# version1.net
KiCad netlist of a schematic drawn in EAGLE
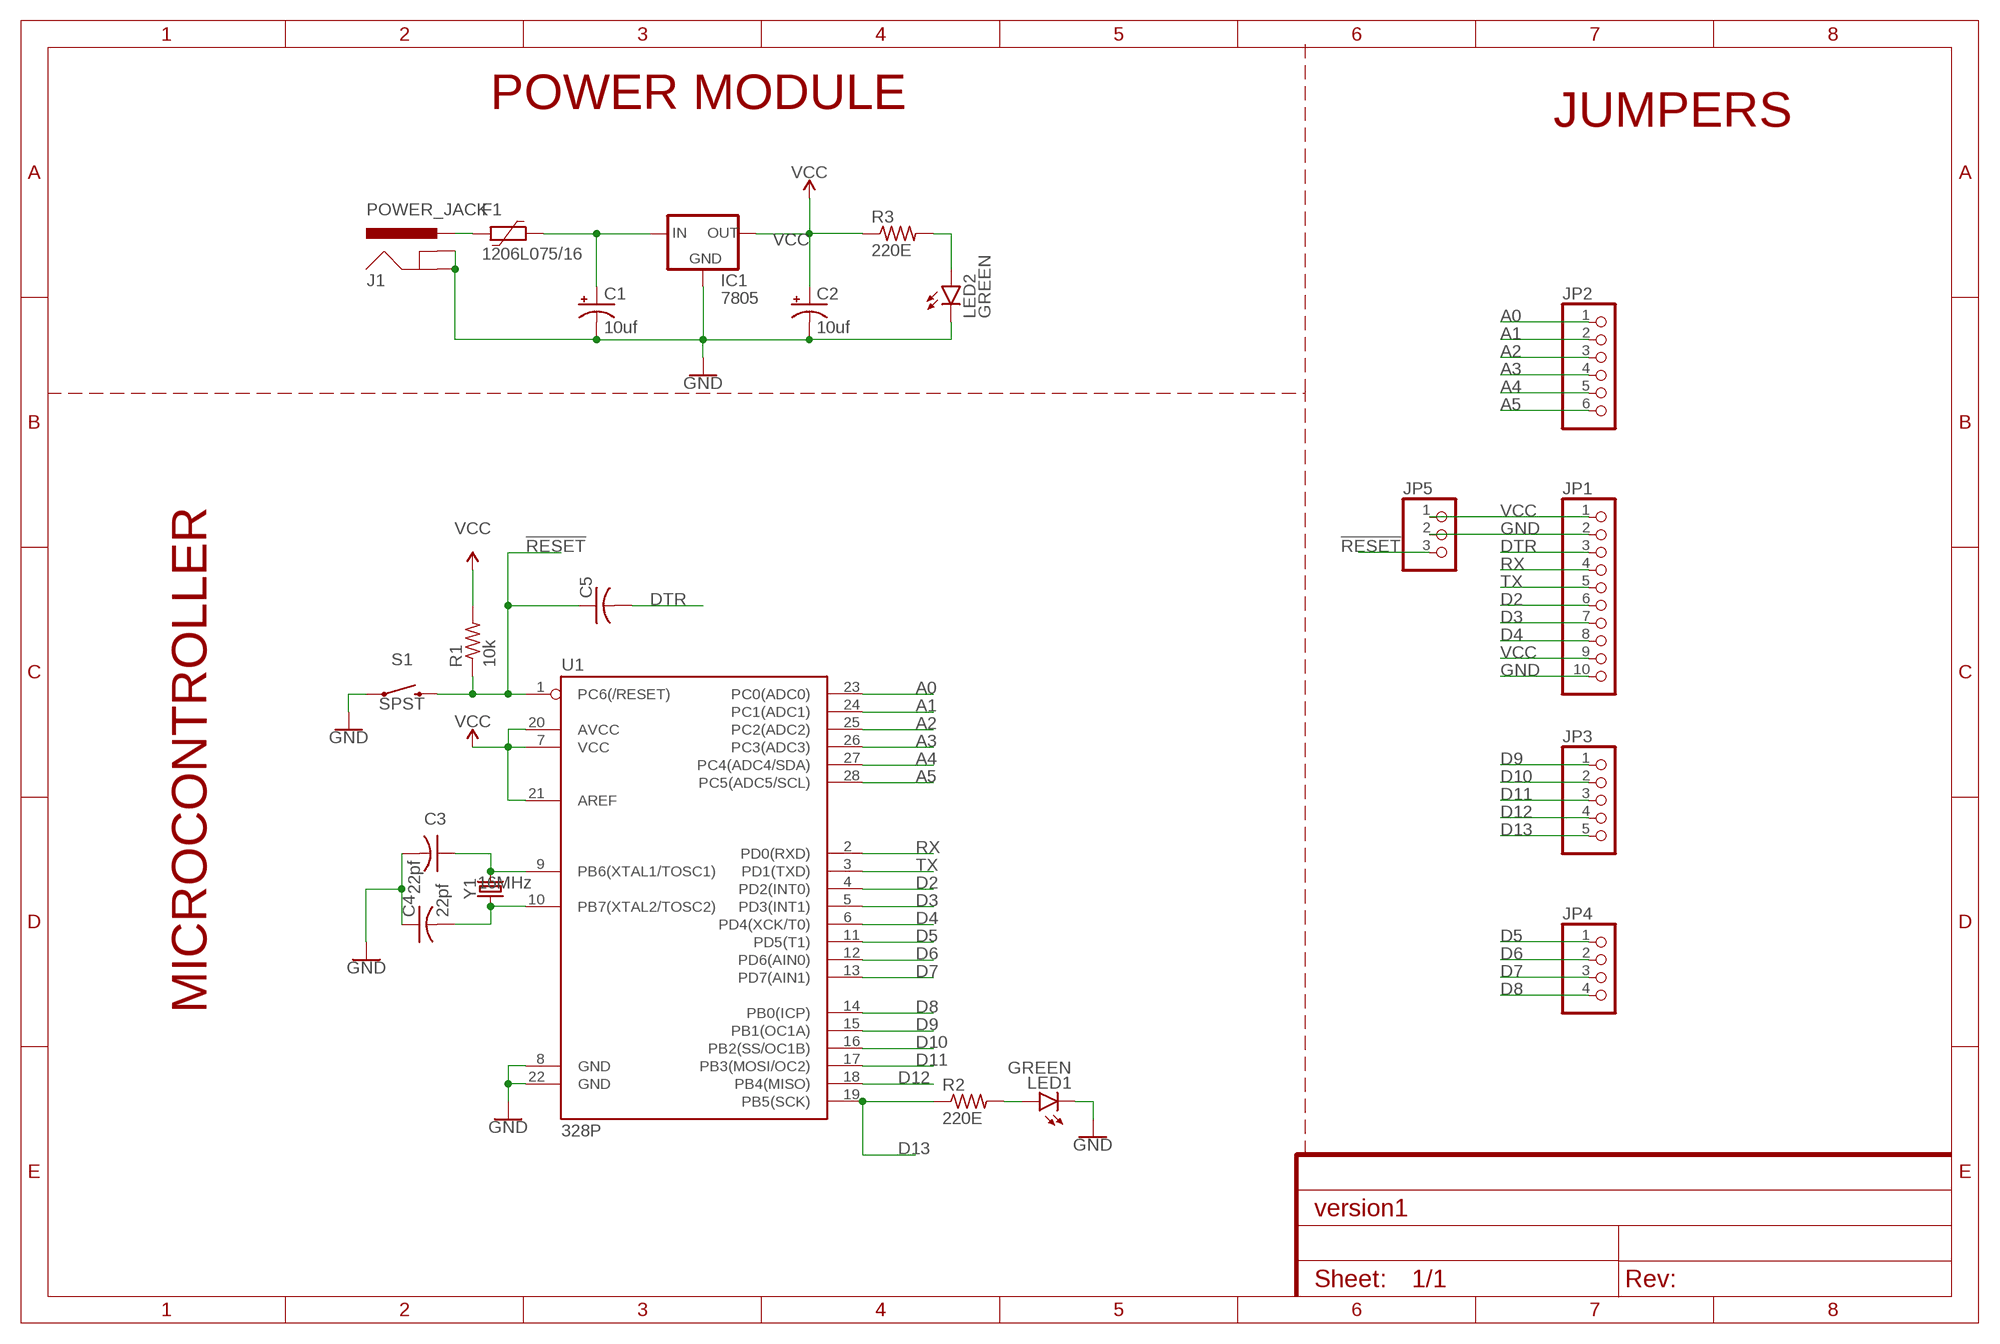
[diagram p0: schematic, sheet 1]

(export (version "E")
  (design (tool "Eeschema 10.0.6"))
  (components
    (comp (ref "C1")
      (value "10uf")
      (footprint "eagle-import:E2,5-6E")
      (libsource (lib "eagle-import") (part "CPOL-USE2,5-6E"))
    )
    (comp (ref "C2")
      (value "10uf")
      (footprint "eagle-import:E2,5-6E")
      (libsource (lib "eagle-import") (part "CPOL-USE2,5-6E"))
    )
    (comp (ref "C3")
      (value "22pf")
      (footprint "eagle-import:C025-024X044")
      (libsource (lib "eagle-import") (part "C-US025-024X044"))
    )
    (comp (ref "C4")
      (value "22pf")
      (footprint "eagle-import:C025-024X044")
      (libsource (lib "eagle-import") (part "C-US025-024X044"))
    )
    (comp (ref "C5")
      (value "C-US025-024X044")
      (footprint "eagle-import:C025-024X044")
      (libsource (lib "eagle-import") (part "C-US025-024X044"))
    )
    (comp (ref "F1")
      (value "1206L075/16")
      (footprint "eagle-import:1206L")
      (fields (field (name "MF") "Littelfuse"))
      (libsource (lib "eagle-import") (part "?1206L075/16"))
    )
    (comp (ref "IC1")
      (value "7805")
      (footprint "eagle-import:78XXS")
      (libsource (lib "eagle-import") (part "78XXS"))
    )
    (comp (ref "J1")
      (value "POWER_JACK")
      (footprint "eagle-import:POWER_JACK_PTH")
      (libsource (lib "eagle-import") (part "POWER_JACK"))
    )
    (comp (ref "JP1")
      (value "PINHD-1X10")
      (footprint "eagle-import:1X10")
      (libsource (lib "eagle-import") (part "PINHD-1X10"))
    )
    (comp (ref "JP2")
      (value "PINHD-1X6")
      (footprint "eagle-import:1X06")
      (libsource (lib "eagle-import") (part "PINHD-1X6"))
    )
    (comp (ref "JP3")
      (value "PINHD-1X5")
      (footprint "eagle-import:1X05")
      (libsource (lib "eagle-import") (part "PINHD-1X5"))
    )
    (comp (ref "JP4")
      (value "PINHD-1X4")
      (footprint "eagle-import:1X04")
      (libsource (lib "eagle-import") (part "PINHD-1X4"))
    )
    (comp (ref "JP5")
      (value "PINHD-1X3")
      (footprint "eagle-import:1X03")
      (libsource (lib "eagle-import") (part "PINHD-1X3"))
    )
    (comp (ref "LED1")
      (value "GREEN")
      (footprint "eagle-import:LED3MM")
      (libsource (lib "eagle-import") (part "LED3MM"))
    )
    (comp (ref "LED2")
      (value "GREEN")
      (footprint "eagle-import:LED3MM")
      (libsource (lib "eagle-import") (part "LED3MM"))
    )
    (comp (ref "R1")
      (value "10k")
      (footprint "eagle-import:0204_7")
      (libsource (lib "eagle-import") (part "R-US_0204/7"))
    )
    (comp (ref "R2")
      (value "220E")
      (footprint "eagle-import:0204_7")
      (libsource (lib "eagle-import") (part "R-US_0204/7"))
    )
    (comp (ref "R3")
      (value "220E")
      (footprint "eagle-import:0204_7")
      (libsource (lib "eagle-import") (part "R-US_0204/7"))
    )
    (comp (ref "S1")
      (value "SPST")
      (footprint "eagle-import:TACTILE_SWITCH_PTH_6.0MM")
      (libsource (lib "eagle-import") (part "MOMENTARY-SWITCH-SPST-PTH-6.0MM"))
    )
    (comp (ref "U1")
      (value "328P")
      (footprint "eagle-import:DIP28")
      (libsource (lib "eagle-import") (part "ATMEGA328P_PDIP"))
    )
    (comp (ref "Y1")
      (value "16MHz")
      (footprint "eagle-import:HC49US")
      (libsource (lib "eagle-import") (part "CRYSTAL-16MHZPTH-HC49US"))
    )
  )
  (nets
    (net (code "1") (name "/A0") (class "Default")
      (node (ref "JP2") (pin "1") (pinfunction "1_1") (pintype "passive"))
      (node (ref "U1") (pin "23") (pinfunction "PC0(ADC0)_23") (pintype "bidirectional"))
    )
    (net (code "2") (name "/A1") (class "Default")
      (node (ref "JP2") (pin "2") (pinfunction "2_2") (pintype "passive"))
      (node (ref "U1") (pin "24") (pinfunction "PC1(ADC1)_24") (pintype "bidirectional"))
    )
    (net (code "3") (name "/A2") (class "Default")
      (node (ref "JP2") (pin "3") (pinfunction "3_3") (pintype "passive"))
      (node (ref "U1") (pin "25") (pinfunction "PC2(ADC2)_25") (pintype "bidirectional"))
    )
    (net (code "4") (name "/A3") (class "Default")
      (node (ref "JP2") (pin "4") (pinfunction "4_4") (pintype "passive"))
      (node (ref "U1") (pin "26") (pinfunction "PC3(ADC3)_26") (pintype "bidirectional"))
    )
    (net (code "5") (name "/A4") (class "Default")
      (node (ref "JP2") (pin "5") (pinfunction "5_5") (pintype "passive"))
      (node (ref "U1") (pin "27") (pinfunction "PC4(ADC4/SDA)_27") (pintype "bidirectional"))
    )
    (net (code "6") (name "/A5") (class "Default")
      (node (ref "JP2") (pin "6") (pinfunction "6_6") (pintype "passive"))
      (node (ref "U1") (pin "28") (pinfunction "PC5(ADC5/SCL)_28") (pintype "bidirectional"))
    )
    (net (code "7") (name "/D2") (class "Default")
      (node (ref "JP1") (pin "6") (pinfunction "6_6") (pintype "passive"))
      (node (ref "U1") (pin "4") (pinfunction "PD2(INT0)_4") (pintype "bidirectional"))
    )
    (net (code "8") (name "/D3") (class "Default")
      (node (ref "JP1") (pin "7") (pinfunction "7_7") (pintype "passive"))
      (node (ref "U1") (pin "5") (pinfunction "PD3(INT1)_5") (pintype "bidirectional"))
    )
    (net (code "9") (name "/D4") (class "Default")
      (node (ref "JP1") (pin "8") (pinfunction "8_8") (pintype "passive"))
      (node (ref "U1") (pin "6") (pinfunction "PD4(XCK/T0)_6") (pintype "bidirectional"))
    )
    (net (code "10") (name "/D5") (class "Default")
      (node (ref "JP4") (pin "1") (pinfunction "1_1") (pintype "passive"))
      (node (ref "U1") (pin "11") (pinfunction "PD5(T1)_11") (pintype "bidirectional"))
    )
    (net (code "11") (name "/D6") (class "Default")
      (node (ref "JP4") (pin "2") (pinfunction "2_2") (pintype "passive"))
      (node (ref "U1") (pin "12") (pinfunction "PD6(AIN0)_12") (pintype "bidirectional"))
    )
    (net (code "12") (name "/D7") (class "Default")
      (node (ref "JP4") (pin "3") (pinfunction "3_3") (pintype "passive"))
      (node (ref "U1") (pin "13") (pinfunction "PD7(AIN1)_13") (pintype "bidirectional"))
    )
    (net (code "13") (name "/D8") (class "Default")
      (node (ref "JP4") (pin "4") (pinfunction "4_4") (pintype "passive"))
      (node (ref "U1") (pin "14") (pinfunction "PB0(ICP)_14") (pintype "bidirectional"))
    )
    (net (code "14") (name "/D9") (class "Default")
      (node (ref "JP3") (pin "1") (pinfunction "1_1") (pintype "passive"))
      (node (ref "U1") (pin "15") (pinfunction "PB1(OC1A)_15") (pintype "bidirectional"))
    )
    (net (code "15") (name "/D10") (class "Default")
      (node (ref "JP3") (pin "2") (pinfunction "2_2") (pintype "passive"))
      (node (ref "U1") (pin "16") (pinfunction "PB2(SS/OC1B)_16") (pintype "bidirectional"))
    )
    (net (code "16") (name "/D11") (class "Default")
      (node (ref "JP3") (pin "3") (pinfunction "3_3") (pintype "passive"))
      (node (ref "U1") (pin "17") (pinfunction "PB3(MOSI/OC2)_17") (pintype "bidirectional"))
    )
    (net (code "17") (name "/D12") (class "Default")
      (node (ref "JP3") (pin "4") (pinfunction "4_4") (pintype "passive"))
      (node (ref "U1") (pin "18") (pinfunction "PB4(MISO)_18") (pintype "bidirectional"))
    )
    (net (code "18") (name "/D13") (class "Default")
      (node (ref "JP3") (pin "5") (pinfunction "5_5") (pintype "passive"))
      (node (ref "R2") (pin "1") (pinfunction "1_1") (pintype "passive"))
      (node (ref "U1") (pin "19") (pinfunction "PB5(SCK)_19") (pintype "bidirectional"))
    )
    (net (code "19") (name "/DTR") (class "Default")
      (node (ref "C5") (pin "2") (pinfunction "2_2") (pintype "passive"))
      (node (ref "JP1") (pin "3") (pinfunction "3_3") (pintype "passive"))
    )
    (net (code "20") (name "/RX") (class "Default")
      (node (ref "JP1") (pin "4") (pinfunction "4_4") (pintype "passive"))
      (node (ref "U1") (pin "2") (pinfunction "PD0(RXD)_2") (pintype "bidirectional"))
    )
    (net (code "21") (name "/TX") (class "Default")
      (node (ref "JP1") (pin "5") (pinfunction "5_5") (pintype "passive"))
      (node (ref "U1") (pin "3") (pinfunction "PD1(TXD)_3") (pintype "bidirectional"))
    )
    (net (code "22") (name "/~{RESET}") (class "Default")
      (node (ref "C5") (pin "1") (pinfunction "1_1") (pintype "passive"))
      (node (ref "JP5") (pin "3") (pinfunction "3_3") (pintype "passive"))
      (node (ref "R1") (pin "1") (pinfunction "1_1") (pintype "passive"))
      (node (ref "S1") (pin "3") (pinfunction "2_3") (pintype "passive"))
      (node (ref "U1") (pin "1") (pinfunction "PC6(/RESET)_1") (pintype "bidirectional"))
    )
    (net (code "23") (name "GND") (class "Default")
      (node (ref "C1") (pin "-") (pinfunction "-_-") (pintype "passive"))
      (node (ref "C2") (pin "-") (pinfunction "-_-") (pintype "passive"))
      (node (ref "C3") (pin "2") (pinfunction "2_2") (pintype "passive"))
      (node (ref "C4") (pin "1") (pinfunction "1_1") (pintype "passive"))
      (node (ref "IC1") (pin "GND") (pinfunction "GND_GND") (pintype "input"))
      (node (ref "J1") (pin "GND") (pinfunction "GND_GND") (pintype "bidirectional"))
      (node (ref "J1") (pin "GNDBREAK") (pinfunction "GNDBREAK_GNDBREAK") (pintype "bidirectional"))
      (node (ref "JP1") (pin "10") (pinfunction "10_10") (pintype "passive"))
      (node (ref "JP1") (pin "2") (pinfunction "2_2") (pintype "passive"))
      (node (ref "JP5") (pin "2") (pinfunction "2_2") (pintype "passive"))
      (node (ref "LED1") (pin "K") (pinfunction "C_K") (pintype "passive"))
      (node (ref "LED2") (pin "K") (pinfunction "C_K") (pintype "passive"))
      (node (ref "S1") (pin "1") (pinfunction "1_1") (pintype "passive"))
      (node (ref "U1") (pin "22") (pinfunction "GND_22") (pintype "bidirectional"))
      (node (ref "U1") (pin "8") (pinfunction "GND_8") (pintype "bidirectional"))
    )
    (net (code "24") (name "Net-(C1-Pad+)") (class "Default")
      (node (ref "C1") (pin "+") (pinfunction "+_+") (pintype "passive"))
      (node (ref "F1") (pin "1") (pinfunction "1_1") (pintype "passive"))
      (node (ref "IC1") (pin "IN") (pinfunction "IN_IN") (pintype "input"))
    )
    (net (code "25") (name "Net-(F1-Pad2)") (class "Default")
      (node (ref "F1") (pin "2") (pinfunction "2_2") (pintype "passive"))
      (node (ref "J1") (pin "PWR") (pinfunction "PWR_PWR") (pintype "bidirectional"))
    )
    (net (code "26") (name "Net-(LED1-PadA)") (class "Default")
      (node (ref "LED1") (pin "A") (pinfunction "A_A") (pintype "passive"))
      (node (ref "R2") (pin "2") (pinfunction "2_2") (pintype "passive"))
    )
    (net (code "27") (name "Net-(LED2-PadA)") (class "Default")
      (node (ref "LED2") (pin "A") (pinfunction "A_A") (pintype "passive"))
      (node (ref "R3") (pin "2") (pinfunction "2_2") (pintype "passive"))
    )
    (net (code "28") (name "Net-(U1-PB6(XTAL1{slash}TOSC1))") (class "Default")
      (node (ref "C3") (pin "1") (pinfunction "1_1") (pintype "passive"))
      (node (ref "U1") (pin "9") (pinfunction "PB6(XTAL1/TOSC1)_9") (pintype "bidirectional"))
      (node (ref "Y1") (pin "2") (pinfunction "2_2") (pintype "passive"))
    )
    (net (code "29") (name "Net-(U1-PB7(XTAL2{slash}TOSC2))") (class "Default")
      (node (ref "C4") (pin "2") (pinfunction "2_2") (pintype "passive"))
      (node (ref "U1") (pin "10") (pinfunction "PB7(XTAL2/TOSC2)_10") (pintype "bidirectional"))
      (node (ref "Y1") (pin "1") (pinfunction "1_1") (pintype "passive"))
    )
    (net (code "30") (name "VCC") (class "Default")
      (node (ref "C2") (pin "+") (pinfunction "+_+") (pintype "passive"))
      (node (ref "IC1") (pin "OUT") (pinfunction "OUT_OUT") (pintype "passive"))
      (node (ref "JP1") (pin "1") (pinfunction "1_1") (pintype "passive"))
      (node (ref "JP1") (pin "9") (pinfunction "9_9") (pintype "passive"))
      (node (ref "JP5") (pin "1") (pinfunction "1_1") (pintype "passive"))
      (node (ref "R1") (pin "2") (pinfunction "2_2") (pintype "passive"))
      (node (ref "R3") (pin "1") (pinfunction "1_1") (pintype "passive"))
      (node (ref "U1") (pin "20") (pinfunction "AVCC_20") (pintype "bidirectional"))
      (node (ref "U1") (pin "21") (pinfunction "AREF_21") (pintype "bidirectional"))
      (node (ref "U1") (pin "7") (pinfunction "VCC_7") (pintype "bidirectional"))
    )
  )
)
